# power_distribution_board.net
KiCad netlist of a schematic drawn in EAGLE
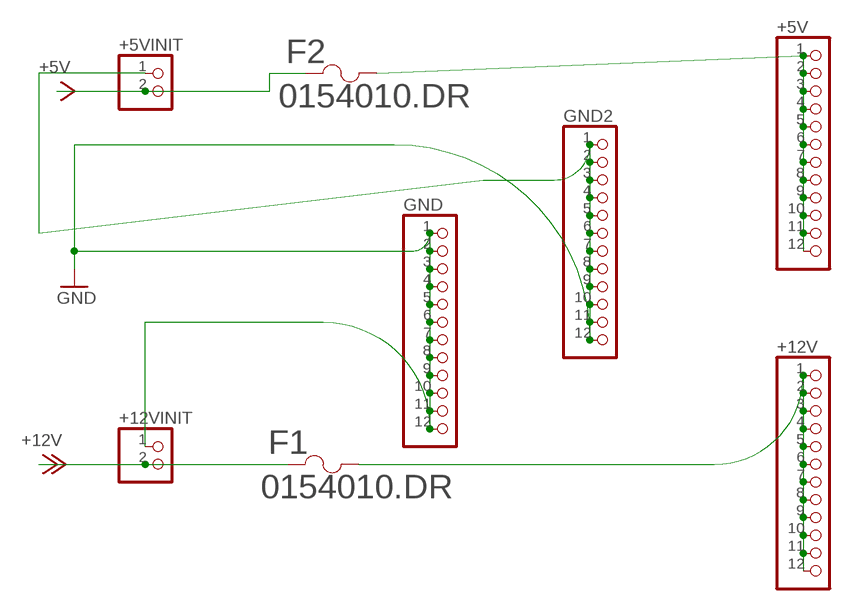
[diagram p0: schematic, sheet 1]

(export (version "E")
  (design (tool "Eeschema 10.0.6"))
  (components
    (comp (ref "+5V")
      (value "TERM_BLOCK_12")
      (footprint "eagle-import:TERM_BLOCK_12")
      (libsource (lib "eagle-import") (part "TERM_BLOCK_12"))
    )
    (comp (ref "+5VINIT")
      (value "TERM_BLOCK_2TERM_BLOCK_2")
      (footprint "eagle-import:1X02")
      (libsource (lib "eagle-import") (part "TERM_BLOCK_2TERM_BLOCK_2"))
    )
    (comp (ref "+12V")
      (value "TERM_BLOCK_12")
      (footprint "eagle-import:TERM_BLOCK_12")
      (libsource (lib "eagle-import") (part "TERM_BLOCK_12"))
    )
    (comp (ref "+12VINIT")
      (value "TERM_BLOCK_2TERM_BLOCK_2")
      (footprint "eagle-import:1X02")
      (libsource (lib "eagle-import") (part "TERM_BLOCK_2TERM_BLOCK_2"))
    )
    (comp (ref "F1")
      (value "0154010.DR")
      (footprint "eagle-import:0154SERIES")
      (libsource (lib "eagle-import") (part "0154010.DR"))
    )
    (comp (ref "F2")
      (value "0154010.DR")
      (footprint "eagle-import:0154SERIES")
      (libsource (lib "eagle-import") (part "0154010.DR"))
    )
    (comp (ref "GND")
      (value "TERM_BLOCK_12")
      (footprint "eagle-import:TERM_BLOCK_12")
      (libsource (lib "eagle-import") (part "TERM_BLOCK_12"))
    )
    (comp (ref "GND2")
      (value "TERM_BLOCK_12")
      (footprint "eagle-import:TERM_BLOCK_12")
      (libsource (lib "eagle-import") (part "TERM_BLOCK_12"))
    )
  )
  (nets
    (net (code "1") (name "+5V") (class "Default")
      (node (ref "+5VINIT") (pin "2") (pinfunction "2_2") (pintype "passive"))
      (node (ref "F2") (pin "1") (pinfunction "1_1") (pintype "passive"))
    )
    (net (code "2") (name "+12V") (class "Default")
      (node (ref "+12VINIT") (pin "2") (pinfunction "2_2") (pintype "passive"))
      (node (ref "F1") (pin "1") (pinfunction "1_1") (pintype "passive"))
    )
    (net (code "3") (name "GND") (class "Default")
      (node (ref "+12VINIT") (pin "1") (pinfunction "1_1") (pintype "passive"))
      (node (ref "+5VINIT") (pin "1") (pinfunction "1_1") (pintype "passive"))
      (node (ref "GND") (pin "1") (pinfunction "1_1") (pintype "passive"))
      (node (ref "GND") (pin "10") (pinfunction "10_10") (pintype "passive"))
      (node (ref "GND") (pin "11") (pinfunction "11_11") (pintype "passive"))
      (node (ref "GND") (pin "12") (pinfunction "12_12") (pintype "passive"))
      (node (ref "GND") (pin "2") (pinfunction "2_2") (pintype "passive"))
      (node (ref "GND") (pin "3") (pinfunction "3_3") (pintype "passive"))
      (node (ref "GND") (pin "4") (pinfunction "4_4") (pintype "passive"))
      (node (ref "GND") (pin "5") (pinfunction "5_5") (pintype "passive"))
      (node (ref "GND") (pin "6") (pinfunction "6_6") (pintype "passive"))
      (node (ref "GND") (pin "7") (pinfunction "7_7") (pintype "passive"))
      (node (ref "GND") (pin "8") (pinfunction "8_8") (pintype "passive"))
      (node (ref "GND") (pin "9") (pinfunction "9_9") (pintype "passive"))
      (node (ref "GND2") (pin "1") (pinfunction "1_1") (pintype "passive"))
      (node (ref "GND2") (pin "10") (pinfunction "10_10") (pintype "passive"))
      (node (ref "GND2") (pin "11") (pinfunction "11_11") (pintype "passive"))
      (node (ref "GND2") (pin "12") (pinfunction "12_12") (pintype "passive"))
      (node (ref "GND2") (pin "2") (pinfunction "2_2") (pintype "passive"))
      (node (ref "GND2") (pin "3") (pinfunction "3_3") (pintype "passive"))
      (node (ref "GND2") (pin "4") (pinfunction "4_4") (pintype "passive"))
      (node (ref "GND2") (pin "5") (pinfunction "5_5") (pintype "passive"))
      (node (ref "GND2") (pin "6") (pinfunction "6_6") (pintype "passive"))
      (node (ref "GND2") (pin "7") (pinfunction "7_7") (pintype "passive"))
      (node (ref "GND2") (pin "8") (pinfunction "8_8") (pintype "passive"))
      (node (ref "GND2") (pin "9") (pinfunction "9_9") (pintype "passive"))
    )
    (net (code "4") (name "Net-(+5V-Pad1)") (class "Default")
      (node (ref "+5V") (pin "1") (pinfunction "1_1") (pintype "passive"))
      (node (ref "+5V") (pin "10") (pinfunction "10_10") (pintype "passive"))
      (node (ref "+5V") (pin "11") (pinfunction "11_11") (pintype "passive"))
      (node (ref "+5V") (pin "12") (pinfunction "12_12") (pintype "passive"))
      (node (ref "+5V") (pin "2") (pinfunction "2_2") (pintype "passive"))
      (node (ref "+5V") (pin "3") (pinfunction "3_3") (pintype "passive"))
      (node (ref "+5V") (pin "4") (pinfunction "4_4") (pintype "passive"))
      (node (ref "+5V") (pin "5") (pinfunction "5_5") (pintype "passive"))
      (node (ref "+5V") (pin "6") (pinfunction "6_6") (pintype "passive"))
      (node (ref "+5V") (pin "7") (pinfunction "7_7") (pintype "passive"))
      (node (ref "+5V") (pin "8") (pinfunction "8_8") (pintype "passive"))
      (node (ref "+5V") (pin "9") (pinfunction "9_9") (pintype "passive"))
      (node (ref "F2") (pin "2") (pinfunction "2_2") (pintype "passive"))
    )
    (net (code "5") (name "Net-(+12V-Pad1)") (class "Default")
      (node (ref "+12V") (pin "1") (pinfunction "1_1") (pintype "passive"))
      (node (ref "+12V") (pin "10") (pinfunction "10_10") (pintype "passive"))
      (node (ref "+12V") (pin "11") (pinfunction "11_11") (pintype "passive"))
      (node (ref "+12V") (pin "12") (pinfunction "12_12") (pintype "passive"))
      (node (ref "+12V") (pin "2") (pinfunction "2_2") (pintype "passive"))
      (node (ref "+12V") (pin "3") (pinfunction "3_3") (pintype "passive"))
      (node (ref "+12V") (pin "4") (pinfunction "4_4") (pintype "passive"))
      (node (ref "+12V") (pin "5") (pinfunction "5_5") (pintype "passive"))
      (node (ref "+12V") (pin "6") (pinfunction "6_6") (pintype "passive"))
      (node (ref "+12V") (pin "7") (pinfunction "7_7") (pintype "passive"))
      (node (ref "+12V") (pin "8") (pinfunction "8_8") (pintype "passive"))
      (node (ref "+12V") (pin "9") (pinfunction "9_9") (pintype "passive"))
      (node (ref "F1") (pin "2") (pinfunction "2_2") (pintype "passive"))
    )
  )
)
